# controller.net
KiCad netlist of a schematic drawn in EAGLE
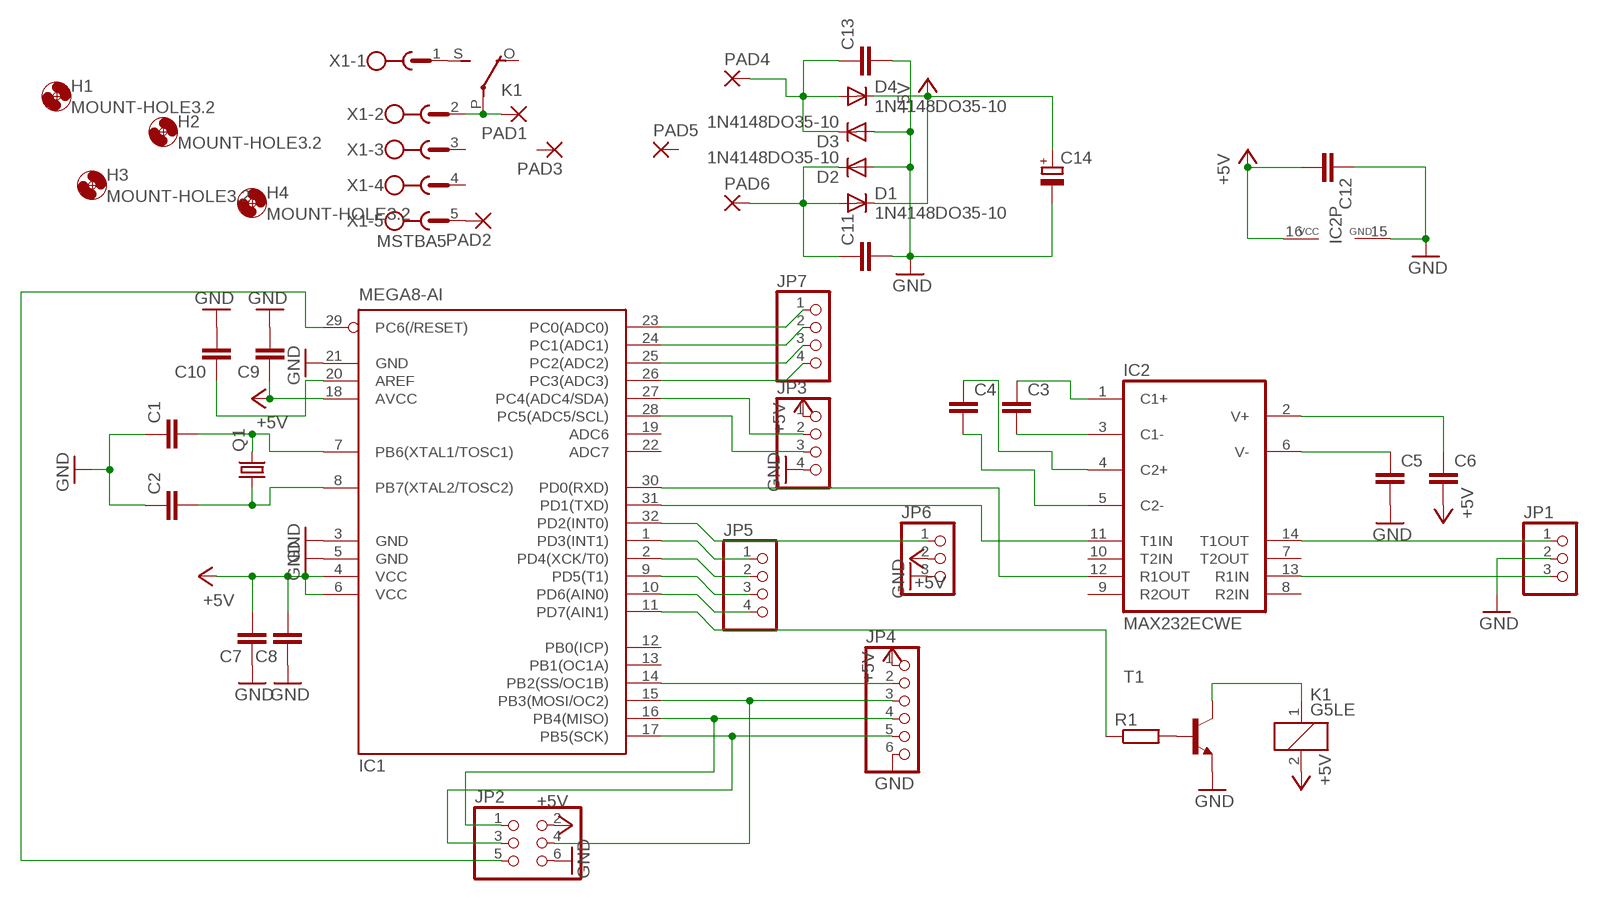
[diagram p0: schematic, sheet 1]

(export (version "E")
  (design (tool "Eeschema 10.0.6"))
  (components
    (comp (ref "C1")
      (value "C-EUC0805")
      (footprint "eagle-import:C0805")
      (libsource (lib "eagle-import") (part "C-EUC0805"))
    )
    (comp (ref "C2")
      (value "C-EUC0805")
      (footprint "eagle-import:C0805")
      (libsource (lib "eagle-import") (part "C-EUC0805"))
    )
    (comp (ref "C3")
      (value "C-EUC0805")
      (footprint "eagle-import:C0805")
      (libsource (lib "eagle-import") (part "C-EUC0805"))
    )
    (comp (ref "C4")
      (value "C-EUC0805")
      (footprint "eagle-import:C0805")
      (libsource (lib "eagle-import") (part "C-EUC0805"))
    )
    (comp (ref "C5")
      (value "C-EUC0805")
      (footprint "eagle-import:C0805")
      (libsource (lib "eagle-import") (part "C-EUC0805"))
    )
    (comp (ref "C6")
      (value "C-EUC0805")
      (footprint "eagle-import:C0805")
      (libsource (lib "eagle-import") (part "C-EUC0805"))
    )
    (comp (ref "C7")
      (value "C-EUC0805")
      (footprint "eagle-import:C0805")
      (libsource (lib "eagle-import") (part "C-EUC0805"))
    )
    (comp (ref "C8")
      (value "C-EUC0805")
      (footprint "eagle-import:C0805")
      (libsource (lib "eagle-import") (part "C-EUC0805"))
    )
    (comp (ref "C9")
      (value "C-EUC0805")
      (footprint "eagle-import:C0805")
      (libsource (lib "eagle-import") (part "C-EUC0805"))
    )
    (comp (ref "C10")
      (value "C-EUC0805")
      (footprint "eagle-import:C0805")
      (libsource (lib "eagle-import") (part "C-EUC0805"))
    )
    (comp (ref "C11")
      (value "C-EU050-025X075")
      (footprint "eagle-import:C050-025X075")
      (libsource (lib "eagle-import") (part "C-EU050-025X075"))
    )
    (comp (ref "C12")
      (value "C-EUC0805")
      (footprint "eagle-import:C0805")
      (libsource (lib "eagle-import") (part "C-EUC0805"))
    )
    (comp (ref "C13")
      (value "C-EU050-025X075")
      (footprint "eagle-import:C050-025X075")
      (libsource (lib "eagle-import") (part "C-EU050-025X075"))
    )
    (comp (ref "C14")
      (value "CPOL-EUE7.5-18")
      (footprint "eagle-import:E7,5-18")
      (libsource (lib "eagle-import") (part "CPOL-EUE7.5-18"))
    )
    (comp (ref "D1")
      (value "1N4148DO35-10")
      (footprint "eagle-import:DO35-10")
      (libsource (lib "eagle-import") (part "1N4148DO35-10"))
    )
    (comp (ref "D2")
      (value "1N4148DO35-10")
      (footprint "eagle-import:DO35-10")
      (libsource (lib "eagle-import") (part "1N4148DO35-10"))
    )
    (comp (ref "D3")
      (value "1N4148DO35-10")
      (footprint "eagle-import:DO35-10")
      (libsource (lib "eagle-import") (part "1N4148DO35-10"))
    )
    (comp (ref "D4")
      (value "1N4148DO35-10")
      (footprint "eagle-import:DO35-10")
      (libsource (lib "eagle-import") (part "1N4148DO35-10"))
    )
    (comp (ref "H1")
      (value "MOUNT-HOLE3.2")
      (footprint "eagle-import:3,2")
      (libsource (lib "eagle-import") (part "MOUNT-HOLE3.2"))
    )
    (comp (ref "H2")
      (value "MOUNT-HOLE3.2")
      (footprint "eagle-import:3,2")
      (libsource (lib "eagle-import") (part "MOUNT-HOLE3.2"))
    )
    (comp (ref "H3")
      (value "MOUNT-HOLE3.2")
      (footprint "eagle-import:3,2")
      (libsource (lib "eagle-import") (part "MOUNT-HOLE3.2"))
    )
    (comp (ref "H4")
      (value "MOUNT-HOLE3.2")
      (footprint "eagle-import:3,2")
      (libsource (lib "eagle-import") (part "MOUNT-HOLE3.2"))
    )
    (comp (ref "IC1")
      (value "MEGA8-AI")
      (footprint "eagle-import:TQFP32-08")
      (fields (field (name "MPN") "ATMEGA8-16AU"))
      (libsource (lib "eagle-import") (part "MEGA8-AI"))
    )
    (comp (ref "IC2")
      (value "MAX232ECWE")
      (footprint "eagle-import:SO16")
      (libsource (lib "eagle-import") (part "MAX232ECWE"))
    )
    (comp (ref "JP1")
      (value "PINHD-1X3")
      (footprint "eagle-import:1X03")
      (libsource (lib "eagle-import") (part "PINHD-1X3"))
    )
    (comp (ref "JP2")
      (value "PINHD-2X3")
      (footprint "eagle-import:2X03")
      (libsource (lib "eagle-import") (part "PINHD-2X3"))
    )
    (comp (ref "JP3")
      (value "PINHD-1X4")
      (footprint "eagle-import:1X04")
      (libsource (lib "eagle-import") (part "PINHD-1X4"))
    )
    (comp (ref "JP4")
      (value "PINHD-1X6")
      (footprint "eagle-import:1X06")
      (libsource (lib "eagle-import") (part "PINHD-1X6"))
    )
    (comp (ref "JP5")
      (value "PINHD-1X4")
      (footprint "eagle-import:1X04")
      (libsource (lib "eagle-import") (part "PINHD-1X4"))
    )
    (comp (ref "JP6")
      (value "PINHD-1X3")
      (footprint "eagle-import:1X03")
      (libsource (lib "eagle-import") (part "PINHD-1X3"))
    )
    (comp (ref "JP7")
      (value "PINHD-1X4")
      (footprint "eagle-import:1X04")
      (libsource (lib "eagle-import") (part "PINHD-1X4"))
    )
    (comp (ref "K1")
      (value "G5LE")
      (footprint "eagle-import:G5LE")
      (libsource (lib "eagle-import") (part "G5LE"))
    )
    (comp (ref "PAD1")
      (value "3,81/1,4")
      (footprint "eagle-import:3,81_1,4")
      (libsource (lib "eagle-import") (part "3,81/1,4"))
    )
    (comp (ref "PAD2")
      (value "3,81/1,4")
      (footprint "eagle-import:3,81_1,4")
      (libsource (lib "eagle-import") (part "3,81/1,4"))
    )
    (comp (ref "PAD3")
      (value "3,81/1,4")
      (footprint "eagle-import:3,81_1,4")
      (libsource (lib "eagle-import") (part "3,81/1,4"))
    )
    (comp (ref "PAD4")
      (value "3,81/1,4")
      (footprint "eagle-import:3,81_1,4")
      (libsource (lib "eagle-import") (part "3,81/1,4"))
    )
    (comp (ref "PAD5")
      (value "3,81/1,4")
      (footprint "eagle-import:3,81_1,4")
      (libsource (lib "eagle-import") (part "3,81/1,4"))
    )
    (comp (ref "PAD6")
      (value "3,81/1,4")
      (footprint "eagle-import:3,81_1,4")
      (libsource (lib "eagle-import") (part "3,81/1,4"))
    )
    (comp (ref "Q1")
      (value "CRYSTALHC49S")
      (footprint "eagle-import:HC49_S")
      (fields (field (name "OC_FARNELL") "1667008"))
      (libsource (lib "eagle-import") (part "CRYSTALHC49S"))
    )
    (comp (ref "R1")
      (value "R-EU_0207/10")
      (footprint "eagle-import:0207_10")
      (libsource (lib "eagle-import") (part "R-EU_0207/10"))
    )
    (comp (ref "T1")
      (value "BC547A-NPN-TO92-CBE")
      (footprint "eagle-import:TO92-CBE")
      (libsource (lib "eagle-import") (part "-NPN-TO92-CBEBC547A"))
    )
    (comp (ref "X1")
      (value "MSTBA5")
      (footprint "eagle-import:MSTBA5")
      (fields (field (name "MPN") "1757271"))
      (libsource (lib "eagle-import") (part "MSTBA5"))
    )
  )
  (nets
    (net (code "1") (name "+5V") (class "Default")
      (node (ref "C12") (pin "2") (pinfunction "2_2") (pintype "passive"))
      (node (ref "C14") (pin "+") (pinfunction "+_+") (pintype "passive"))
      (node (ref "C6") (pin "2") (pinfunction "2_2") (pintype "passive"))
      (node (ref "C7") (pin "2") (pinfunction "2_2") (pintype "passive"))
      (node (ref "C8") (pin "2") (pinfunction "2_2") (pintype "passive"))
      (node (ref "C9") (pin "1") (pinfunction "1_1") (pintype "passive"))
      (node (ref "D1") (pin "C") (pinfunction "C_C") (pintype "passive"))
      (node (ref "D4") (pin "C") (pinfunction "C_C") (pintype "passive"))
      (node (ref "IC1") (pin "18") (pinfunction "AVCC_18") (pintype "power_in"))
      (node (ref "IC1") (pin "4") (pinfunction "VCC_4") (pintype "power_in"))
      (node (ref "IC1") (pin "6") (pinfunction "VCC_6") (pintype "power_in"))
      (node (ref "IC2") (pin "16") (pinfunction "VCC_16") (pintype "power_in"))
      (node (ref "JP2") (pin "2") (pinfunction "2_2") (pintype "passive"))
      (node (ref "JP3") (pin "1") (pinfunction "1_1") (pintype "passive"))
      (node (ref "JP4") (pin "1") (pinfunction "1_1") (pintype "passive"))
      (node (ref "JP6") (pin "2") (pinfunction "2_2") (pintype "passive"))
      (node (ref "K1") (pin "2") (pinfunction "2_2") (pintype "passive"))
    )
    (net (code "2") (name "GND") (class "Default")
      (node (ref "C1") (pin "1") (pinfunction "1_1") (pintype "passive"))
      (node (ref "C10") (pin "2") (pinfunction "2_2") (pintype "passive"))
      (node (ref "C11") (pin "2") (pinfunction "2_2") (pintype "passive"))
      (node (ref "C12") (pin "1") (pinfunction "1_1") (pintype "passive"))
      (node (ref "C13") (pin "2") (pinfunction "2_2") (pintype "passive"))
      (node (ref "C14") (pin "-") (pinfunction "-_-") (pintype "passive"))
      (node (ref "C2") (pin "1") (pinfunction "1_1") (pintype "passive"))
      (node (ref "C5") (pin "2") (pinfunction "2_2") (pintype "passive"))
      (node (ref "C7") (pin "1") (pinfunction "1_1") (pintype "passive"))
      (node (ref "C8") (pin "1") (pinfunction "1_1") (pintype "passive"))
      (node (ref "C9") (pin "2") (pinfunction "2_2") (pintype "passive"))
      (node (ref "D2") (pin "A") (pinfunction "A_A") (pintype "passive"))
      (node (ref "D3") (pin "A") (pinfunction "A_A") (pintype "passive"))
      (node (ref "IC1") (pin "21") (pinfunction "GND_21") (pintype "power_in"))
      (node (ref "IC1") (pin "3") (pinfunction "GND_3") (pintype "power_in"))
      (node (ref "IC1") (pin "5") (pinfunction "GND_5") (pintype "power_in"))
      (node (ref "IC2") (pin "15") (pinfunction "GND_15") (pintype "power_in"))
      (node (ref "JP1") (pin "2") (pinfunction "2_2") (pintype "passive"))
      (node (ref "JP2") (pin "6") (pinfunction "6_6") (pintype "passive"))
      (node (ref "JP3") (pin "4") (pinfunction "4_4") (pintype "passive"))
      (node (ref "JP4") (pin "6") (pinfunction "6_6") (pintype "passive"))
      (node (ref "JP6") (pin "3") (pinfunction "3_3") (pintype "passive"))
      (node (ref "T1") (pin "E") (pinfunction "E_E") (pintype "passive"))
    )
    (net (code "3") (name "Net-(IC1-AREF)") (class "Default")
      (node (ref "C10") (pin "1") (pinfunction "1_1") (pintype "passive"))
      (node (ref "IC1") (pin "20") (pinfunction "AREF_20") (pintype "passive"))
    )
    (net (code "4") (name "Net-(IC1-PB2(SS{slash}OC1B))") (class "Default")
      (node (ref "IC1") (pin "14") (pinfunction "PB2(SS/OC1B)_14") (pintype "bidirectional"))
      (node (ref "JP4") (pin "2") (pinfunction "2_2") (pintype "passive"))
    )
    (net (code "5") (name "Net-(IC1-PB3(MOSI{slash}OC2))") (class "Default")
      (node (ref "IC1") (pin "15") (pinfunction "PB3(MOSI/OC2)_15") (pintype "bidirectional"))
      (node (ref "JP2") (pin "4") (pinfunction "4_4") (pintype "passive"))
      (node (ref "JP4") (pin "3") (pinfunction "3_3") (pintype "passive"))
    )
    (net (code "6") (name "Net-(IC1-PB4(MISO))") (class "Default")
      (node (ref "IC1") (pin "16") (pinfunction "PB4(MISO)_16") (pintype "bidirectional"))
      (node (ref "JP2") (pin "1") (pinfunction "1_1") (pintype "passive"))
      (node (ref "JP4") (pin "4") (pinfunction "4_4") (pintype "passive"))
    )
    (net (code "7") (name "Net-(IC1-PB5(SCK))") (class "Default")
      (node (ref "IC1") (pin "17") (pinfunction "PB5(SCK)_17") (pintype "bidirectional"))
      (node (ref "JP2") (pin "3") (pinfunction "3_3") (pintype "passive"))
      (node (ref "JP4") (pin "5") (pinfunction "5_5") (pintype "passive"))
    )
    (net (code "8") (name "Net-(IC1-PB6(XTAL1{slash}TOSC1))") (class "Default")
      (node (ref "C1") (pin "2") (pinfunction "2_2") (pintype "passive"))
      (node (ref "IC1") (pin "7") (pinfunction "PB6(XTAL1/TOSC1)_7") (pintype "bidirectional"))
      (node (ref "Q1") (pin "2") (pinfunction "2_2") (pintype "passive"))
    )
    (net (code "9") (name "Net-(IC1-PB7(XTAL2{slash}TOSC2))") (class "Default")
      (node (ref "C2") (pin "2") (pinfunction "2_2") (pintype "passive"))
      (node (ref "IC1") (pin "8") (pinfunction "PB7(XTAL2/TOSC2)_8") (pintype "bidirectional"))
      (node (ref "Q1") (pin "1") (pinfunction "1_1") (pintype "passive"))
    )
    (net (code "10") (name "Net-(IC1-PC0(ADC0))") (class "Default")
      (node (ref "IC1") (pin "23") (pinfunction "PC0(ADC0)_23") (pintype "bidirectional"))
      (node (ref "JP7") (pin "1") (pinfunction "1_1") (pintype "passive"))
    )
    (net (code "11") (name "Net-(IC1-PC1(ADC1))") (class "Default")
      (node (ref "IC1") (pin "24") (pinfunction "PC1(ADC1)_24") (pintype "bidirectional"))
      (node (ref "JP7") (pin "2") (pinfunction "2_2") (pintype "passive"))
    )
    (net (code "12") (name "Net-(IC1-PC2(ADC2))") (class "Default")
      (node (ref "IC1") (pin "25") (pinfunction "PC2(ADC2)_25") (pintype "bidirectional"))
      (node (ref "JP7") (pin "3") (pinfunction "3_3") (pintype "passive"))
    )
    (net (code "13") (name "Net-(IC1-PC3(ADC3))") (class "Default")
      (node (ref "IC1") (pin "26") (pinfunction "PC3(ADC3)_26") (pintype "bidirectional"))
      (node (ref "JP7") (pin "4") (pinfunction "4_4") (pintype "passive"))
    )
    (net (code "14") (name "Net-(IC1-PC4(ADC4{slash}SDA))") (class "Default")
      (node (ref "IC1") (pin "27") (pinfunction "PC4(ADC4/SDA)_27") (pintype "bidirectional"))
      (node (ref "JP3") (pin "2") (pinfunction "2_2") (pintype "passive"))
    )
    (net (code "15") (name "Net-(IC1-PC5(ADC5{slash}SCL))") (class "Default")
      (node (ref "IC1") (pin "28") (pinfunction "PC5(ADC5/SCL)_28") (pintype "bidirectional"))
      (node (ref "JP3") (pin "3") (pinfunction "3_3") (pintype "passive"))
    )
    (net (code "16") (name "Net-(IC1-PC6({slash}RESET))") (class "Default")
      (node (ref "IC1") (pin "29") (pinfunction "PC6(/RESET)_29") (pintype "bidirectional"))
      (node (ref "JP2") (pin "5") (pinfunction "5_5") (pintype "passive"))
    )
    (net (code "17") (name "Net-(IC1-PD0(RXD))") (class "Default")
      (node (ref "IC1") (pin "30") (pinfunction "PD0(RXD)_30") (pintype "bidirectional"))
      (node (ref "IC2") (pin "12") (pinfunction "R1OUT_12") (pintype "output"))
    )
    (net (code "18") (name "Net-(IC1-PD1(TXD))") (class "Default")
      (node (ref "IC1") (pin "31") (pinfunction "PD1(TXD)_31") (pintype "bidirectional"))
      (node (ref "IC2") (pin "11") (pinfunction "T1IN_11") (pintype "input"))
    )
    (net (code "19") (name "Net-(IC1-PD2(INT0))") (class "Default")
      (node (ref "IC1") (pin "32") (pinfunction "PD2(INT0)_32") (pintype "bidirectional"))
      (node (ref "JP6") (pin "1") (pinfunction "1_1") (pintype "passive"))
    )
    (net (code "20") (name "Net-(IC1-PD3(INT1))") (class "Default")
      (node (ref "IC1") (pin "1") (pinfunction "PD3(INT1)_1") (pintype "bidirectional"))
      (node (ref "JP5") (pin "1") (pinfunction "1_1") (pintype "passive"))
    )
    (net (code "21") (name "Net-(IC1-PD4(XCK{slash}T0))") (class "Default")
      (node (ref "IC1") (pin "2") (pinfunction "PD4(XCK/T0)_2") (pintype "bidirectional"))
      (node (ref "JP5") (pin "2") (pinfunction "2_2") (pintype "passive"))
    )
    (net (code "22") (name "Net-(IC1-PD5(T1))") (class "Default")
      (node (ref "IC1") (pin "9") (pinfunction "PD5(T1)_9") (pintype "bidirectional"))
      (node (ref "JP5") (pin "3") (pinfunction "3_3") (pintype "passive"))
    )
    (net (code "23") (name "Net-(IC1-PD6(AIN0))") (class "Default")
      (node (ref "IC1") (pin "10") (pinfunction "PD6(AIN0)_10") (pintype "bidirectional"))
      (node (ref "JP5") (pin "4") (pinfunction "4_4") (pintype "passive"))
    )
    (net (code "24") (name "Net-(IC1-PD7(AIN1))") (class "Default")
      (node (ref "IC1") (pin "11") (pinfunction "PD7(AIN1)_11") (pintype "bidirectional"))
      (node (ref "R1") (pin "1") (pinfunction "1_1") (pintype "passive"))
    )
    (net (code "25") (name "Net-(IC2A-C1+)") (class "Default")
      (node (ref "C3") (pin "1") (pinfunction "1_1") (pintype "passive"))
      (node (ref "IC2") (pin "1") (pinfunction "C1+_1") (pintype "bidirectional"))
    )
    (net (code "26") (name "Net-(IC2A-C1-)") (class "Default")
      (node (ref "C3") (pin "2") (pinfunction "2_2") (pintype "passive"))
      (node (ref "IC2") (pin "3") (pinfunction "C1-_3") (pintype "bidirectional"))
    )
    (net (code "27") (name "Net-(IC2A-C2+)") (class "Default")
      (node (ref "C4") (pin "1") (pinfunction "1_1") (pintype "passive"))
      (node (ref "IC2") (pin "4") (pinfunction "C2+_4") (pintype "bidirectional"))
    )
    (net (code "28") (name "Net-(IC2A-C2-)") (class "Default")
      (node (ref "C4") (pin "2") (pinfunction "2_2") (pintype "passive"))
      (node (ref "IC2") (pin "5") (pinfunction "C2-_5") (pintype "bidirectional"))
    )
    (net (code "29") (name "Net-(IC2A-R1IN)") (class "Default")
      (node (ref "IC2") (pin "13") (pinfunction "R1IN_13") (pintype "input"))
      (node (ref "JP1") (pin "3") (pinfunction "3_3") (pintype "passive"))
    )
    (net (code "30") (name "Net-(IC2A-T1OUT)") (class "Default")
      (node (ref "IC2") (pin "14") (pinfunction "T1OUT_14") (pintype "output"))
      (node (ref "JP1") (pin "1") (pinfunction "1_1") (pintype "passive"))
    )
    (net (code "31") (name "Net-(IC2A-V+)") (class "Default")
      (node (ref "C6") (pin "1") (pinfunction "1_1") (pintype "passive"))
      (node (ref "IC2") (pin "2") (pinfunction "V+_2") (pintype "bidirectional"))
    )
    (net (code "32") (name "Net-(IC2A-V-)") (class "Default")
      (node (ref "C5") (pin "1") (pinfunction "1_1") (pintype "passive"))
      (node (ref "IC2") (pin "6") (pinfunction "V-_6") (pintype "bidirectional"))
    )
    (net (code "33") (name "Net-(K1-Pad1)") (class "Default")
      (node (ref "K1") (pin "1") (pinfunction "1_1") (pintype "passive"))
      (node (ref "T1") (pin "C") (pinfunction "C_C") (pintype "passive"))
    )
    (net (code "34") (name "Net-(K1-PadS)") (class "Default")
      (node (ref "K1") (pin "S") (pinfunction "S_S") (pintype "passive"))
      (node (ref "X1") (pin "1") (pinfunction "1_1") (pintype "passive"))
    )
    (net (code "35") (name "Net-(PAD1-P)") (class "Default")
      (node (ref "K1") (pin "P") (pinfunction "P_P") (pintype "passive"))
      (node (ref "PAD1") (pin "1") (pinfunction "P_1") (pintype "passive"))
      (node (ref "X1") (pin "2") (pinfunction "1_2") (pintype "passive"))
    )
    (net (code "36") (name "Net-(PAD2-P)") (class "Default")
      (node (ref "PAD2") (pin "1") (pinfunction "P_1") (pintype "passive"))
      (node (ref "X1") (pin "5") (pinfunction "1_5") (pintype "passive"))
    )
    (net (code "37") (name "Net-(PAD4-P)") (class "Default")
      (node (ref "C13") (pin "1") (pinfunction "1_1") (pintype "passive"))
      (node (ref "D3") (pin "C") (pinfunction "C_C") (pintype "passive"))
      (node (ref "D4") (pin "A") (pinfunction "A_A") (pintype "passive"))
      (node (ref "PAD4") (pin "1") (pinfunction "P_1") (pintype "passive"))
    )
    (net (code "38") (name "Net-(PAD6-P)") (class "Default")
      (node (ref "C11") (pin "1") (pinfunction "1_1") (pintype "passive"))
      (node (ref "D1") (pin "A") (pinfunction "A_A") (pintype "passive"))
      (node (ref "D2") (pin "C") (pinfunction "C_C") (pintype "passive"))
      (node (ref "PAD6") (pin "1") (pinfunction "P_1") (pintype "passive"))
    )
    (net (code "39") (name "Net-(R1-Pad2)") (class "Default")
      (node (ref "R1") (pin "2") (pinfunction "2_2") (pintype "passive"))
      (node (ref "T1") (pin "B") (pinfunction "B_B") (pintype "passive"))
    )
    (net (code "40") (name "unconnected-(IC1-ADC6-Pad19)") (class "Default")
      (node (ref "IC1") (pin "19") (pinfunction "ADC6_19") (pintype "bidirectional"))
    )
    (net (code "41") (name "unconnected-(IC1-ADC7-Pad22)") (class "Default")
      (node (ref "IC1") (pin "22") (pinfunction "ADC7_22") (pintype "bidirectional"))
    )
    (net (code "42") (name "unconnected-(IC1-PB0(ICP)-Pad12)") (class "Default")
      (node (ref "IC1") (pin "12") (pinfunction "PB0(ICP)_12") (pintype "bidirectional"))
    )
    (net (code "43") (name "unconnected-(IC1-PB1(OC1A)-Pad13)") (class "Default")
      (node (ref "IC1") (pin "13") (pinfunction "PB1(OC1A)_13") (pintype "bidirectional"))
    )
    (net (code "44") (name "unconnected-(IC2A-R2IN-Pad8)") (class "Default")
      (node (ref "IC2") (pin "8") (pinfunction "R2IN_8") (pintype "input"))
    )
    (net (code "45") (name "unconnected-(IC2A-R2OUT-Pad9)") (class "Default")
      (node (ref "IC2") (pin "9") (pinfunction "R2OUT_9") (pintype "output"))
    )
    (net (code "46") (name "unconnected-(IC2A-T2IN-Pad10)") (class "Default")
      (node (ref "IC2") (pin "10") (pinfunction "T2IN_10") (pintype "input"))
    )
    (net (code "47") (name "unconnected-(IC2A-T2OUT-Pad7)") (class "Default")
      (node (ref "IC2") (pin "7") (pinfunction "T2OUT_7") (pintype "output"))
    )
    (net (code "48") (name "unconnected-(K1-PadO)") (class "Default")
      (node (ref "K1") (pin "O") (pinfunction "O_O") (pintype "passive"))
    )
    (net (code "49") (name "unconnected-(PAD3-P-Pad1)") (class "Default")
      (node (ref "PAD3") (pin "1") (pinfunction "P_1") (pintype "passive"))
    )
    (net (code "50") (name "unconnected-(PAD5-P-Pad1)") (class "Default")
      (node (ref "PAD5") (pin "1") (pinfunction "P_1") (pintype "passive"))
    )
    (net (code "51") (name "unconnected-(X1C-1-Pad3)") (class "Default")
      (node (ref "X1") (pin "3") (pinfunction "1_3") (pintype "passive"))
    )
    (net (code "52") (name "unconnected-(X1D-1-Pad4)") (class "Default")
      (node (ref "X1") (pin "4") (pinfunction "1_4") (pintype "passive"))
    )
  )
)
